# lvds4ch.net
KiCad netlist of a schematic drawn in Altium Designer
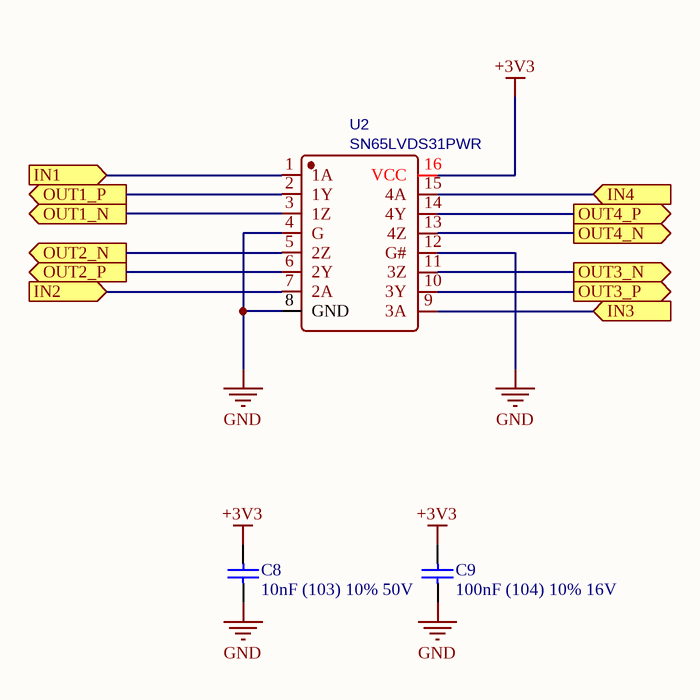
[diagram p0: lvds4ch.SchDoc]

(export (version "E")
  (design (tool "Eeschema 10.0.6"))
  (components
    (comp (ref "C8")
      (value "10nF (103) 10% 50V")
      (footprint "0402_C")
      (description "贴片电容")
      (libsource (lib "Miscellaneous Devices LC") (part "0402 10nF (103) 10% 50V"))
    )
    (comp (ref "C9")
      (value "100nF (104) 10% 16V")
      (footprint "0402_C")
      (description "贴片电容")
      (libsource (lib "Miscellaneous Devices LC") (part "0402 100nF (104) 10% 16V"))
    )
    (comp (ref "U2")
      (value "SN65LVDS31PWR")
      (footprint "TSSOP-16_L5.0-W4.4-P0.65-LS6.4-BL")
      (fields (field (name "BOM_SUPPLIER PART") "C181630") (field (name "CONTRIBUTOR") "LCSC"))
      (libsource (lib "altium-import") (part "root_0_SN65LVDS31PWR_"))
    )
  )
  (nets
    (net (code "1") (name "+3V3") (class "Default")
      (node (ref "C8") (pin "2") (pinfunction "2_2") (pintype "passive"))
      (node (ref "C9") (pin "2") (pinfunction "2_2") (pintype "passive"))
      (node (ref "U2") (pin "16") (pinfunction "VCC_16") (pintype "passive"))
    )
    (net (code "2") (name "/IN1") (class "Default")
      (node (ref "U2") (pin "1") (pinfunction "1A_1") (pintype "passive"))
    )
    (net (code "3") (name "/IN2") (class "Default")
      (node (ref "U2") (pin "7") (pinfunction "2A_7") (pintype "passive"))
    )
    (net (code "4") (name "/IN3") (class "Default")
      (node (ref "U2") (pin "9") (pinfunction "3A_9") (pintype "passive"))
    )
    (net (code "5") (name "/IN4") (class "Default")
      (node (ref "U2") (pin "15") (pinfunction "4A_15") (pintype "passive"))
    )
    (net (code "6") (name "/OUT1_N") (class "Default")
      (node (ref "U2") (pin "3") (pinfunction "1Z_3") (pintype "passive"))
    )
    (net (code "7") (name "/OUT1_P") (class "Default")
      (node (ref "U2") (pin "2") (pinfunction "1Y_2") (pintype "passive"))
    )
    (net (code "8") (name "/OUT2_N") (class "Default")
      (node (ref "U2") (pin "5") (pinfunction "2Z_5") (pintype "passive"))
    )
    (net (code "9") (name "/OUT2_P") (class "Default")
      (node (ref "U2") (pin "6") (pinfunction "2Y_6") (pintype "passive"))
    )
    (net (code "10") (name "/OUT3_N") (class "Default")
      (node (ref "U2") (pin "11") (pinfunction "3Z_11") (pintype "passive"))
    )
    (net (code "11") (name "/OUT3_P") (class "Default")
      (node (ref "U2") (pin "10") (pinfunction "3Y_10") (pintype "passive"))
    )
    (net (code "12") (name "/OUT4_N") (class "Default")
      (node (ref "U2") (pin "13") (pinfunction "4Z_13") (pintype "passive"))
    )
    (net (code "13") (name "/OUT4_P") (class "Default")
      (node (ref "U2") (pin "14") (pinfunction "4Y_14") (pintype "passive"))
    )
    (net (code "14") (name "GND") (class "Default")
      (node (ref "C8") (pin "1") (pinfunction "1_1") (pintype "passive"))
      (node (ref "C9") (pin "1") (pinfunction "1_1") (pintype "passive"))
      (node (ref "U2") (pin "12") (pinfunction "G#_12") (pintype "passive"))
      (node (ref "U2") (pin "4") (pinfunction "G_4") (pintype "passive"))
      (node (ref "U2") (pin "8") (pinfunction "GND_8") (pintype "passive"))
    )
  )
)
